# M708X.net
KiCad netlist of a schematic drawn in EAGLE
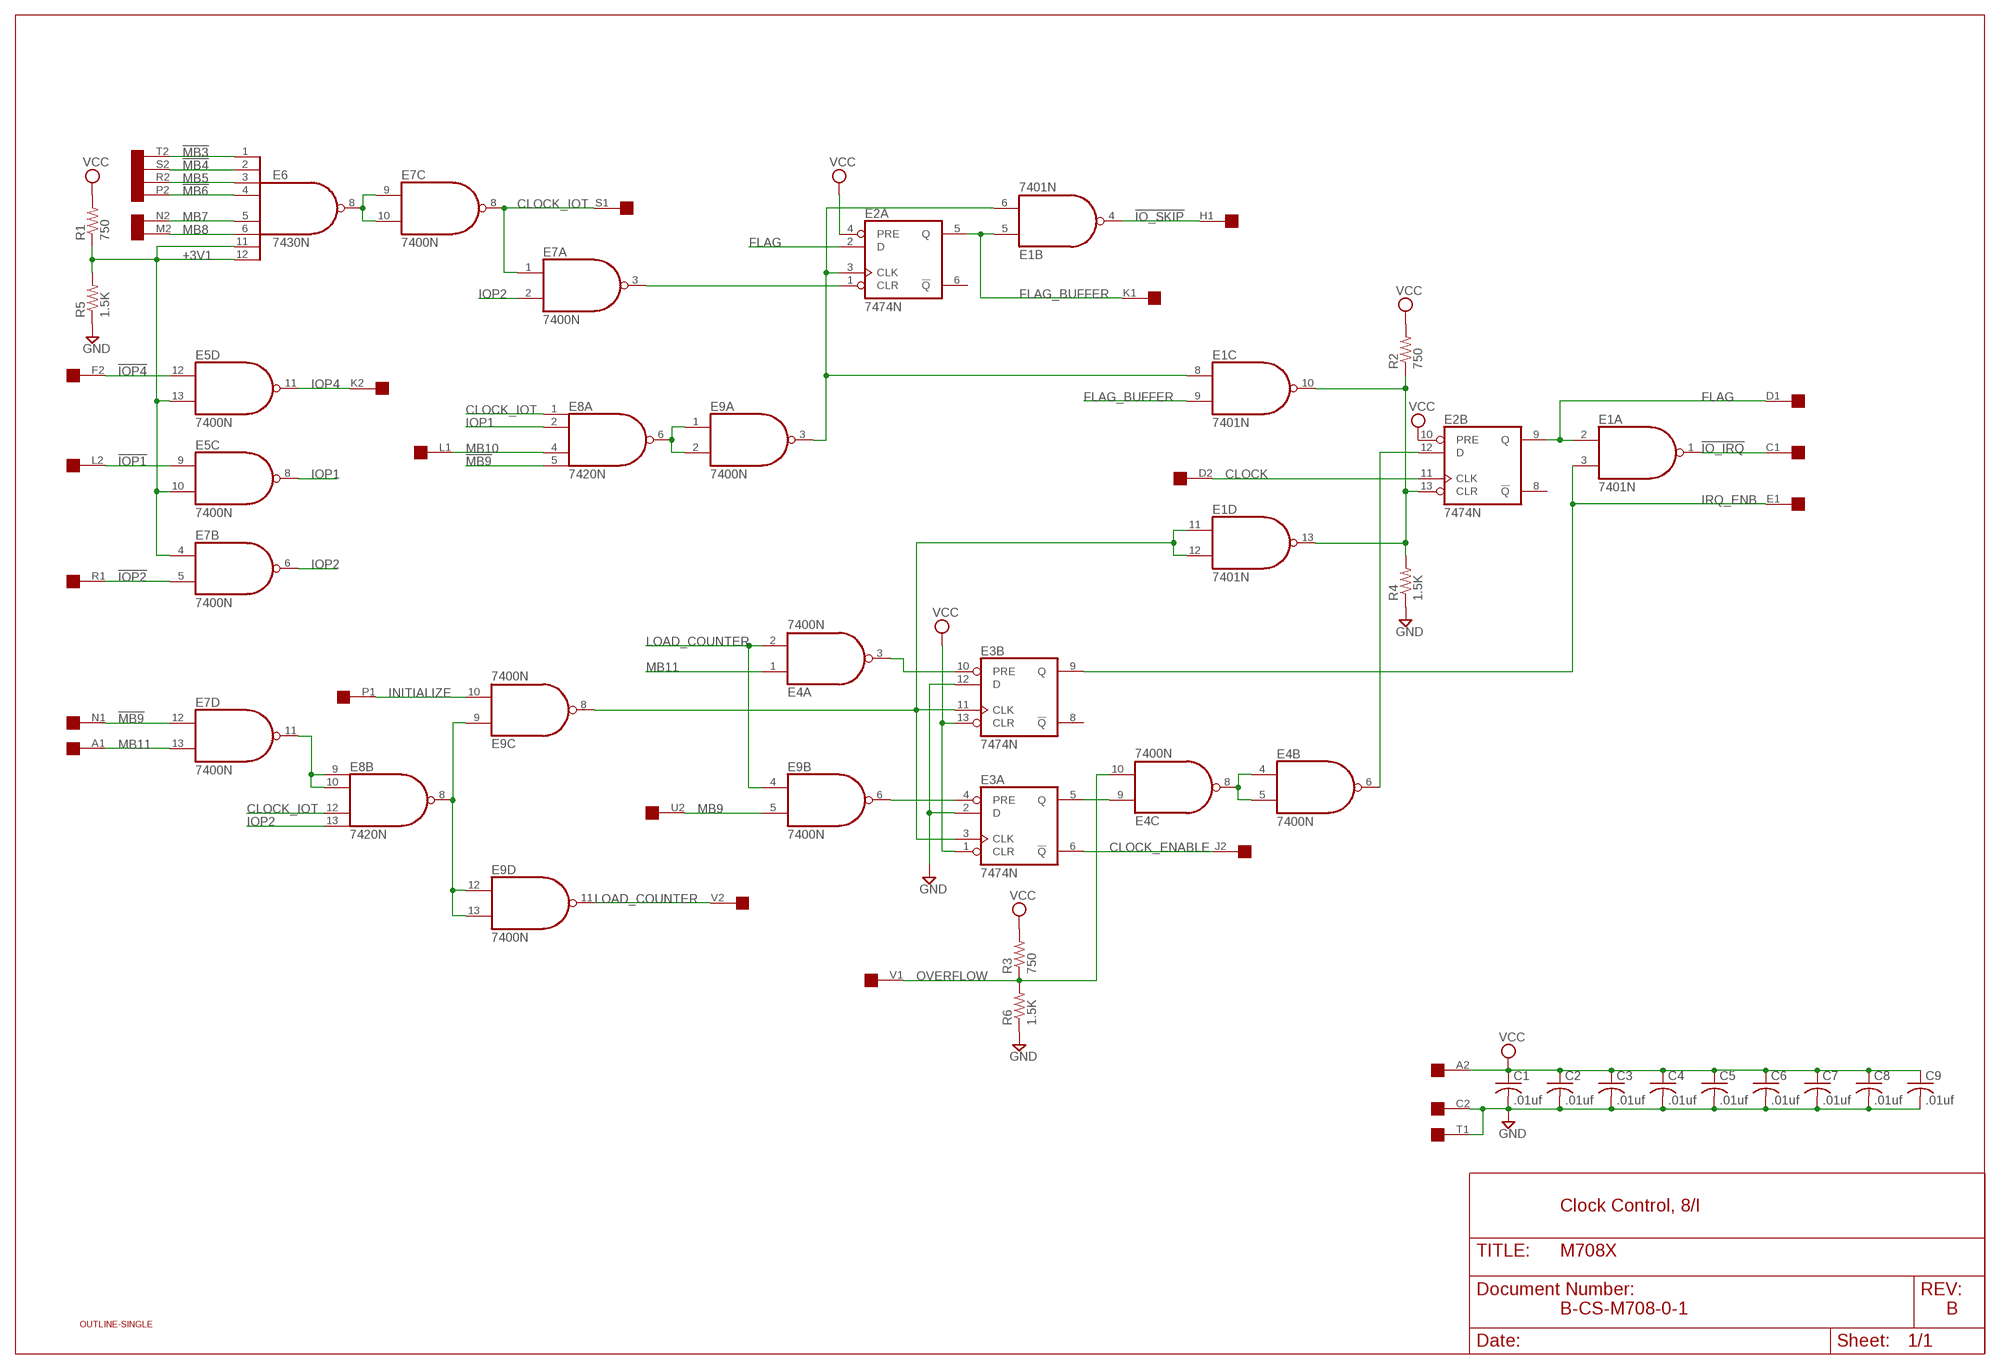
[diagram p0: schematic, sheet 1]

(export (version "E")
  (design (tool "Eeschema 10.0.6"))
  (components
    (comp (ref "C1")
      (value ".01uf")
      (footprint "eagle-import:C075-032X103")
      (libsource (lib "eagle-import") (part "C-US075-032X103"))
    )
    (comp (ref "C2")
      (value ".01uf")
      (footprint "eagle-import:C075-032X103")
      (libsource (lib "eagle-import") (part "C-US075-032X103"))
    )
    (comp (ref "C3")
      (value ".01uf")
      (footprint "eagle-import:C075-032X103")
      (libsource (lib "eagle-import") (part "C-US075-032X103"))
    )
    (comp (ref "C4")
      (value ".01uf")
      (footprint "eagle-import:C075-032X103")
      (libsource (lib "eagle-import") (part "C-US075-032X103"))
    )
    (comp (ref "C5")
      (value ".01uf")
      (footprint "eagle-import:C075-032X103")
      (libsource (lib "eagle-import") (part "C-US075-032X103"))
    )
    (comp (ref "C6")
      (value ".01uf")
      (footprint "eagle-import:C075-032X103")
      (libsource (lib "eagle-import") (part "C-US075-032X103"))
    )
    (comp (ref "C7")
      (value ".01uf")
      (footprint "eagle-import:C075-032X103")
      (libsource (lib "eagle-import") (part "C-US075-032X103"))
    )
    (comp (ref "C8")
      (value ".01uf")
      (footprint "eagle-import:C075-032X103")
      (libsource (lib "eagle-import") (part "C-US075-032X103"))
    )
    (comp (ref "C9")
      (value ".01uf")
      (footprint "eagle-import:C075-032X103")
      (libsource (lib "eagle-import") (part "C-US075-032X103"))
    )
    (comp (ref "E1")
      (value "7401N")
      (footprint "eagle-import:DIL14")
      (libsource (lib "eagle-import") (part "7401NLS"))
    )
    (comp (ref "E2")
      (value "7474N")
      (footprint "eagle-import:DIL14")
      (libsource (lib "eagle-import") (part "7474NS"))
    )
    (comp (ref "E3")
      (value "7474N")
      (footprint "eagle-import:DIL14")
      (libsource (lib "eagle-import") (part "7474NS"))
    )
    (comp (ref "E4")
      (value "7400N")
      (footprint "eagle-import:DIL14")
      (libsource (lib "eagle-import") (part "7400N"))
    )
    (comp (ref "E5")
      (value "7400N")
      (footprint "eagle-import:DIL14")
      (libsource (lib "eagle-import") (part "7400N"))
    )
    (comp (ref "E6")
      (value "7430N")
      (footprint "eagle-import:DIL14")
      (libsource (lib "eagle-import") (part "7430N"))
    )
    (comp (ref "E7")
      (value "7400N")
      (footprint "eagle-import:DIL14")
      (libsource (lib "eagle-import") (part "7400N"))
    )
    (comp (ref "E8")
      (value "7420N")
      (footprint "eagle-import:DIL14")
      (libsource (lib "eagle-import") (part "7420NS"))
    )
    (comp (ref "E9")
      (value "7400N")
      (footprint "eagle-import:DIL14")
      (libsource (lib "eagle-import") (part "7400N"))
    )
    (comp (ref "R1")
      (value "750")
      (footprint "eagle-import:0207_10")
      (libsource (lib "eagle-import") (part "R-US_0207/10"))
    )
    (comp (ref "R2")
      (value "750")
      (footprint "eagle-import:0207_10")
      (libsource (lib "eagle-import") (part "R-US_0207/10"))
    )
    (comp (ref "R3")
      (value "750")
      (footprint "eagle-import:0207_10")
      (libsource (lib "eagle-import") (part "R-US_0207/10"))
    )
    (comp (ref "R4")
      (value "1.5K")
      (footprint "eagle-import:0207_10")
      (libsource (lib "eagle-import") (part "R-US_0207/10"))
    )
    (comp (ref "R5")
      (value "1.5K")
      (footprint "eagle-import:0207_10")
      (libsource (lib "eagle-import") (part "R-US_0207/10"))
    )
    (comp (ref "R6")
      (value "1.5K")
      (footprint "eagle-import:0207_10")
      (libsource (lib "eagle-import") (part "R-US_0207/10"))
    )
    (comp (ref "U$1")
      (value "SINGLE")
      (footprint "eagle-import:EDGE-CON2")
      (libsource (lib "eagle-import") (part "SINGLE"))
    )
    (comp (ref "U$4")
      (value "OUTLINE-SINGLE")
      (footprint "eagle-import:SINGLE")
      (libsource (lib "eagle-import") (part "OUTLINE-SINGLE"))
    )
  )
  (nets
    (net (code "1") (name "/+3V1") (class "Default")
      (node (ref "E5") (pin "10") (pinfunction "I1_10") (pintype "input"))
      (node (ref "E5") (pin "13") (pinfunction "I1_13") (pintype "input"))
      (node (ref "E6") (pin "11") (pinfunction "I6_11") (pintype "input"))
      (node (ref "E6") (pin "12") (pinfunction "I7_12") (pintype "input"))
      (node (ref "E7") (pin "4") (pinfunction "I0_4") (pintype "input"))
      (node (ref "R1") (pin "1") (pinfunction "1_1") (pintype "passive"))
      (node (ref "R5") (pin "2") (pinfunction "2_2") (pintype "passive"))
    )
    (net (code "2") (name "/CLOCK") (class "Default")
      (node (ref "E2") (pin "11") (pinfunction "CLK_11") (pintype "input"))
      (node (ref "U$1") (pin "D2") (pinfunction "1_D2") (pintype "bidirectional"))
    )
    (net (code "3") (name "/CLOCK_ENABLE") (class "Default")
      (node (ref "E3") (pin "6") (pinfunction "~{Q}_6") (pintype "output"))
      (node (ref "U$1") (pin "J2") (pinfunction "1_J2") (pintype "bidirectional"))
    )
    (net (code "4") (name "/CLOCK_IOT") (class "Default")
      (node (ref "E7") (pin "1") (pinfunction "I0_1") (pintype "input"))
      (node (ref "E7") (pin "8") (pinfunction "O_8") (pintype "output"))
      (node (ref "E8") (pin "1") (pinfunction "I0_1") (pintype "input"))
      (node (ref "E8") (pin "12") (pinfunction "I2_12") (pintype "input"))
      (node (ref "U$1") (pin "S1") (pinfunction "1_S1") (pintype "bidirectional"))
    )
    (net (code "5") (name "/FLAG") (class "Default")
      (node (ref "E1") (pin "2") (pinfunction "I0_2") (pintype "input"))
      (node (ref "E2") (pin "2") (pinfunction "D_2") (pintype "input"))
      (node (ref "E2") (pin "9") (pinfunction "Q_9") (pintype "output"))
      (node (ref "U$1") (pin "D1") (pinfunction "1_D1") (pintype "bidirectional"))
    )
    (net (code "6") (name "/FLAG_BUFFER") (class "Default")
      (node (ref "E1") (pin "5") (pinfunction "I0_5") (pintype "input"))
      (node (ref "E1") (pin "9") (pinfunction "I1_9") (pintype "input"))
      (node (ref "E2") (pin "5") (pinfunction "Q_5") (pintype "output"))
      (node (ref "U$1") (pin "K1") (pinfunction "1_K1") (pintype "bidirectional"))
    )
    (net (code "7") (name "/INITIALIZE") (class "Default")
      (node (ref "E9") (pin "10") (pinfunction "I1_10") (pintype "input"))
      (node (ref "U$1") (pin "P1") (pinfunction "1_P1") (pintype "bidirectional"))
    )
    (net (code "8") (name "/IOP1") (class "Default")
      (node (ref "E5") (pin "8") (pinfunction "O_8") (pintype "output"))
      (node (ref "E8") (pin "2") (pinfunction "I1_2") (pintype "input"))
    )
    (net (code "9") (name "/IOP2") (class "Default")
      (node (ref "E7") (pin "2") (pinfunction "I1_2") (pintype "input"))
      (node (ref "E7") (pin "6") (pinfunction "O_6") (pintype "output"))
      (node (ref "E8") (pin "13") (pinfunction "I3_13") (pintype "input"))
    )
    (net (code "10") (name "/IOP4") (class "Default")
      (node (ref "E5") (pin "11") (pinfunction "O_11") (pintype "output"))
      (node (ref "U$1") (pin "K2") (pinfunction "1_K2") (pintype "bidirectional"))
    )
    (net (code "11") (name "/IRQ_ENB") (class "Default")
      (node (ref "E1") (pin "3") (pinfunction "I1_3") (pintype "input"))
      (node (ref "E3") (pin "9") (pinfunction "Q_9") (pintype "output"))
      (node (ref "U$1") (pin "E1") (pinfunction "1_E1") (pintype "bidirectional"))
    )
    (net (code "12") (name "/LOAD_COUNTER") (class "Default")
      (node (ref "E4") (pin "2") (pinfunction "I1_2") (pintype "input"))
      (node (ref "E9") (pin "11") (pinfunction "O_11") (pintype "output"))
      (node (ref "E9") (pin "4") (pinfunction "I0_4") (pintype "input"))
      (node (ref "U$1") (pin "V2") (pinfunction "1_V2") (pintype "bidirectional"))
    )
    (net (code "13") (name "/MB5") (class "Default")
      (node (ref "E6") (pin "3") (pinfunction "I2_3") (pintype "input"))
      (node (ref "U$1") (pin "R2") (pinfunction "1_R2") (pintype "bidirectional"))
    )
    (net (code "14") (name "/MB7") (class "Default")
      (node (ref "E6") (pin "5") (pinfunction "I4_5") (pintype "input"))
      (node (ref "U$1") (pin "N2") (pinfunction "1_N2") (pintype "bidirectional"))
    )
    (net (code "15") (name "/MB8") (class "Default")
      (node (ref "E6") (pin "6") (pinfunction "I5_6") (pintype "input"))
      (node (ref "U$1") (pin "M2") (pinfunction "1_M2") (pintype "bidirectional"))
    )
    (net (code "16") (name "/MB9") (class "Default")
      (node (ref "E9") (pin "5") (pinfunction "I1_5") (pintype "input"))
      (node (ref "U$1") (pin "U2") (pinfunction "1_U2") (pintype "bidirectional"))
    )
    (net (code "17") (name "/MB10") (class "Default")
      (node (ref "E8") (pin "4") (pinfunction "I2_4") (pintype "input"))
      (node (ref "U$1") (pin "L1") (pinfunction "1_L1") (pintype "bidirectional"))
    )
    (net (code "18") (name "/MB11") (class "Default")
      (node (ref "E4") (pin "1") (pinfunction "I0_1") (pintype "input"))
      (node (ref "E7") (pin "13") (pinfunction "I1_13") (pintype "input"))
      (node (ref "U$1") (pin "A1") (pinfunction "1_A1") (pintype "bidirectional"))
    )
    (net (code "19") (name "/OVERFLOW") (class "Default")
      (node (ref "E4") (pin "10") (pinfunction "I1_10") (pintype "input"))
      (node (ref "R3") (pin "1") (pinfunction "1_1") (pintype "passive"))
      (node (ref "R6") (pin "2") (pinfunction "2_2") (pintype "passive"))
      (node (ref "U$1") (pin "V1") (pinfunction "1_V1") (pintype "bidirectional"))
    )
    (net (code "20") (name "/~{IOP1}") (class "Default")
      (node (ref "E5") (pin "9") (pinfunction "I0_9") (pintype "input"))
      (node (ref "U$1") (pin "L2") (pinfunction "1_L2") (pintype "bidirectional"))
    )
    (net (code "21") (name "/~{IOP2}") (class "Default")
      (node (ref "E7") (pin "5") (pinfunction "I1_5") (pintype "input"))
      (node (ref "U$1") (pin "R1") (pinfunction "1_R1") (pintype "bidirectional"))
    )
    (net (code "22") (name "/~{IOP4}") (class "Default")
      (node (ref "E5") (pin "12") (pinfunction "I0_12") (pintype "input"))
      (node (ref "U$1") (pin "F2") (pinfunction "1_F2") (pintype "bidirectional"))
    )
    (net (code "23") (name "/~{IO_IRQ}") (class "Default")
      (node (ref "E1") (pin "1") (pinfunction "O_1") (pintype "open_collector"))
      (node (ref "U$1") (pin "C1") (pinfunction "1_C1") (pintype "bidirectional"))
    )
    (net (code "24") (name "/~{IO_SKIP}") (class "Default")
      (node (ref "E1") (pin "4") (pinfunction "O_4") (pintype "open_collector"))
      (node (ref "U$1") (pin "H1") (pinfunction "1_H1") (pintype "bidirectional"))
    )
    (net (code "25") (name "/~{MB3}") (class "Default")
      (node (ref "E6") (pin "1") (pinfunction "I0_1") (pintype "input"))
      (node (ref "U$1") (pin "T2") (pinfunction "1_T2") (pintype "bidirectional"))
    )
    (net (code "26") (name "/~{MB4}") (class "Default")
      (node (ref "E6") (pin "2") (pinfunction "I1_2") (pintype "input"))
      (node (ref "U$1") (pin "S2") (pinfunction "1_S2") (pintype "bidirectional"))
    )
    (net (code "27") (name "/~{MB6}") (class "Default")
      (node (ref "E6") (pin "4") (pinfunction "I3_4") (pintype "input"))
      (node (ref "U$1") (pin "P2") (pinfunction "1_P2") (pintype "bidirectional"))
    )
    (net (code "28") (name "/~{MB9}") (class "Default")
      (node (ref "E7") (pin "12") (pinfunction "I0_12") (pintype "input"))
      (node (ref "E8") (pin "5") (pinfunction "I3_5") (pintype "input"))
      (node (ref "U$1") (pin "N1") (pinfunction "1_N1") (pintype "bidirectional"))
    )
    (net (code "29") (name "GND") (class "Default")
      (node (ref "C1") (pin "2") (pinfunction "2_2") (pintype "passive"))
      (node (ref "C2") (pin "2") (pinfunction "2_2") (pintype "passive"))
      (node (ref "C3") (pin "2") (pinfunction "2_2") (pintype "passive"))
      (node (ref "C4") (pin "2") (pinfunction "2_2") (pintype "passive"))
      (node (ref "C5") (pin "2") (pinfunction "2_2") (pintype "passive"))
      (node (ref "C6") (pin "2") (pinfunction "2_2") (pintype "passive"))
      (node (ref "C7") (pin "2") (pinfunction "2_2") (pintype "passive"))
      (node (ref "C8") (pin "2") (pinfunction "2_2") (pintype "passive"))
      (node (ref "C9") (pin "2") (pinfunction "2_2") (pintype "passive"))
      (node (ref "E3") (pin "12") (pinfunction "D_12") (pintype "input"))
      (node (ref "E3") (pin "2") (pinfunction "D_2") (pintype "input"))
      (node (ref "R4") (pin "1") (pinfunction "1_1") (pintype "passive"))
      (node (ref "R5") (pin "1") (pinfunction "1_1") (pintype "passive"))
      (node (ref "R6") (pin "1") (pinfunction "1_1") (pintype "passive"))
      (node (ref "U$1") (pin "C2") (pinfunction "1_C2") (pintype "bidirectional"))
      (node (ref "U$1") (pin "T1") (pinfunction "1_T1") (pintype "bidirectional"))
    )
    (net (code "30") (name "Net-(E1B-I1)") (class "Default")
      (node (ref "E1") (pin "6") (pinfunction "I1_6") (pintype "input"))
      (node (ref "E1") (pin "8") (pinfunction "I0_8") (pintype "input"))
      (node (ref "E2") (pin "3") (pinfunction "CLK_3") (pintype "input"))
      (node (ref "E9") (pin "3") (pinfunction "O_3") (pintype "output"))
    )
    (net (code "31") (name "Net-(E1C-O)") (class "Default")
      (node (ref "E1") (pin "10") (pinfunction "O_10") (pintype "open_collector"))
      (node (ref "E1") (pin "13") (pinfunction "O_13") (pintype "open_collector"))
      (node (ref "E2") (pin "13") (pinfunction "CLR_13") (pintype "input"))
      (node (ref "R2") (pin "1") (pinfunction "1_1") (pintype "passive"))
      (node (ref "R4") (pin "2") (pinfunction "2_2") (pintype "passive"))
    )
    (net (code "32") (name "Net-(E1D-I0)") (class "Default")
      (node (ref "E1") (pin "11") (pinfunction "I0_11") (pintype "input"))
      (node (ref "E1") (pin "12") (pinfunction "I1_12") (pintype "input"))
      (node (ref "E3") (pin "11") (pinfunction "CLK_11") (pintype "input"))
      (node (ref "E3") (pin "3") (pinfunction "CLK_3") (pintype "input"))
      (node (ref "E9") (pin "8") (pinfunction "O_8") (pintype "output"))
    )
    (net (code "33") (name "Net-(E2A-CLR)") (class "Default")
      (node (ref "E2") (pin "1") (pinfunction "CLR_1") (pintype "input"))
      (node (ref "E7") (pin "3") (pinfunction "O_3") (pintype "output"))
    )
    (net (code "34") (name "Net-(E2B-D)") (class "Default")
      (node (ref "E2") (pin "12") (pinfunction "D_12") (pintype "input"))
      (node (ref "E4") (pin "6") (pinfunction "O_6") (pintype "output"))
    )
    (net (code "35") (name "Net-(E3A-PRE)") (class "Default")
      (node (ref "E3") (pin "4") (pinfunction "PRE_4") (pintype "input"))
      (node (ref "E9") (pin "6") (pinfunction "O_6") (pintype "output"))
    )
    (net (code "36") (name "Net-(E3A-Q)") (class "Default")
      (node (ref "E3") (pin "5") (pinfunction "Q_5") (pintype "output"))
      (node (ref "E4") (pin "9") (pinfunction "I0_9") (pintype "input"))
    )
    (net (code "37") (name "Net-(E3B-PRE)") (class "Default")
      (node (ref "E3") (pin "10") (pinfunction "PRE_10") (pintype "input"))
      (node (ref "E4") (pin "3") (pinfunction "O_3") (pintype "output"))
    )
    (net (code "38") (name "Net-(E4B-I0)") (class "Default")
      (node (ref "E4") (pin "4") (pinfunction "I0_4") (pintype "input"))
      (node (ref "E4") (pin "5") (pinfunction "I1_5") (pintype "input"))
      (node (ref "E4") (pin "8") (pinfunction "O_8") (pintype "output"))
    )
    (net (code "39") (name "Net-(E6A-O)") (class "Default")
      (node (ref "E6") (pin "8") (pinfunction "O_8") (pintype "output"))
      (node (ref "E7") (pin "10") (pinfunction "I1_10") (pintype "input"))
      (node (ref "E7") (pin "9") (pinfunction "I0_9") (pintype "input"))
    )
    (net (code "40") (name "Net-(E7D-O)") (class "Default")
      (node (ref "E7") (pin "11") (pinfunction "O_11") (pintype "output"))
      (node (ref "E8") (pin "10") (pinfunction "I1_10") (pintype "input"))
      (node (ref "E8") (pin "9") (pinfunction "I0_9") (pintype "input"))
    )
    (net (code "41") (name "Net-(E8A-O)") (class "Default")
      (node (ref "E8") (pin "6") (pinfunction "O_6") (pintype "output"))
      (node (ref "E9") (pin "1") (pinfunction "I0_1") (pintype "input"))
      (node (ref "E9") (pin "2") (pinfunction "I1_2") (pintype "input"))
    )
    (net (code "42") (name "Net-(E8B-O)") (class "Default")
      (node (ref "E8") (pin "8") (pinfunction "O_8") (pintype "output"))
      (node (ref "E9") (pin "12") (pinfunction "I0_12") (pintype "input"))
      (node (ref "E9") (pin "13") (pinfunction "I1_13") (pintype "input"))
      (node (ref "E9") (pin "9") (pinfunction "I0_9") (pintype "input"))
    )
    (net (code "43") (name "VCC") (class "Default")
      (node (ref "C1") (pin "1") (pinfunction "1_1") (pintype "passive"))
      (node (ref "C2") (pin "1") (pinfunction "1_1") (pintype "passive"))
      (node (ref "C3") (pin "1") (pinfunction "1_1") (pintype "passive"))
      (node (ref "C4") (pin "1") (pinfunction "1_1") (pintype "passive"))
      (node (ref "C5") (pin "1") (pinfunction "1_1") (pintype "passive"))
      (node (ref "C6") (pin "1") (pinfunction "1_1") (pintype "passive"))
      (node (ref "C7") (pin "1") (pinfunction "1_1") (pintype "passive"))
      (node (ref "C8") (pin "1") (pinfunction "1_1") (pintype "passive"))
      (node (ref "C9") (pin "1") (pinfunction "1_1") (pintype "passive"))
      (node (ref "E2") (pin "10") (pinfunction "PRE_10") (pintype "input"))
      (node (ref "E2") (pin "4") (pinfunction "PRE_4") (pintype "input"))
      (node (ref "E3") (pin "1") (pinfunction "CLR_1") (pintype "input"))
      (node (ref "E3") (pin "13") (pinfunction "CLR_13") (pintype "input"))
      (node (ref "R1") (pin "2") (pinfunction "2_2") (pintype "passive"))
      (node (ref "R2") (pin "2") (pinfunction "2_2") (pintype "passive"))
      (node (ref "R3") (pin "2") (pinfunction "2_2") (pintype "passive"))
      (node (ref "U$1") (pin "A2") (pinfunction "1_A2") (pintype "bidirectional"))
    )
    (net (code "44") (name "unconnected-(E2A-~{Q}-Pad6)") (class "Default")
      (node (ref "E2") (pin "6") (pinfunction "~{Q}_6") (pintype "output"))
    )
    (net (code "45") (name "unconnected-(E2B-~{Q}-Pad8)") (class "Default")
      (node (ref "E2") (pin "8") (pinfunction "~{Q}_8") (pintype "output"))
    )
    (net (code "46") (name "unconnected-(E3B-~{Q}-Pad8)") (class "Default")
      (node (ref "E3") (pin "8") (pinfunction "~{Q}_8") (pintype "output"))
    )
  )
)
